# sai_arduinoPinMap.net
KiCad netlist of a schematic drawn in Altium Designer
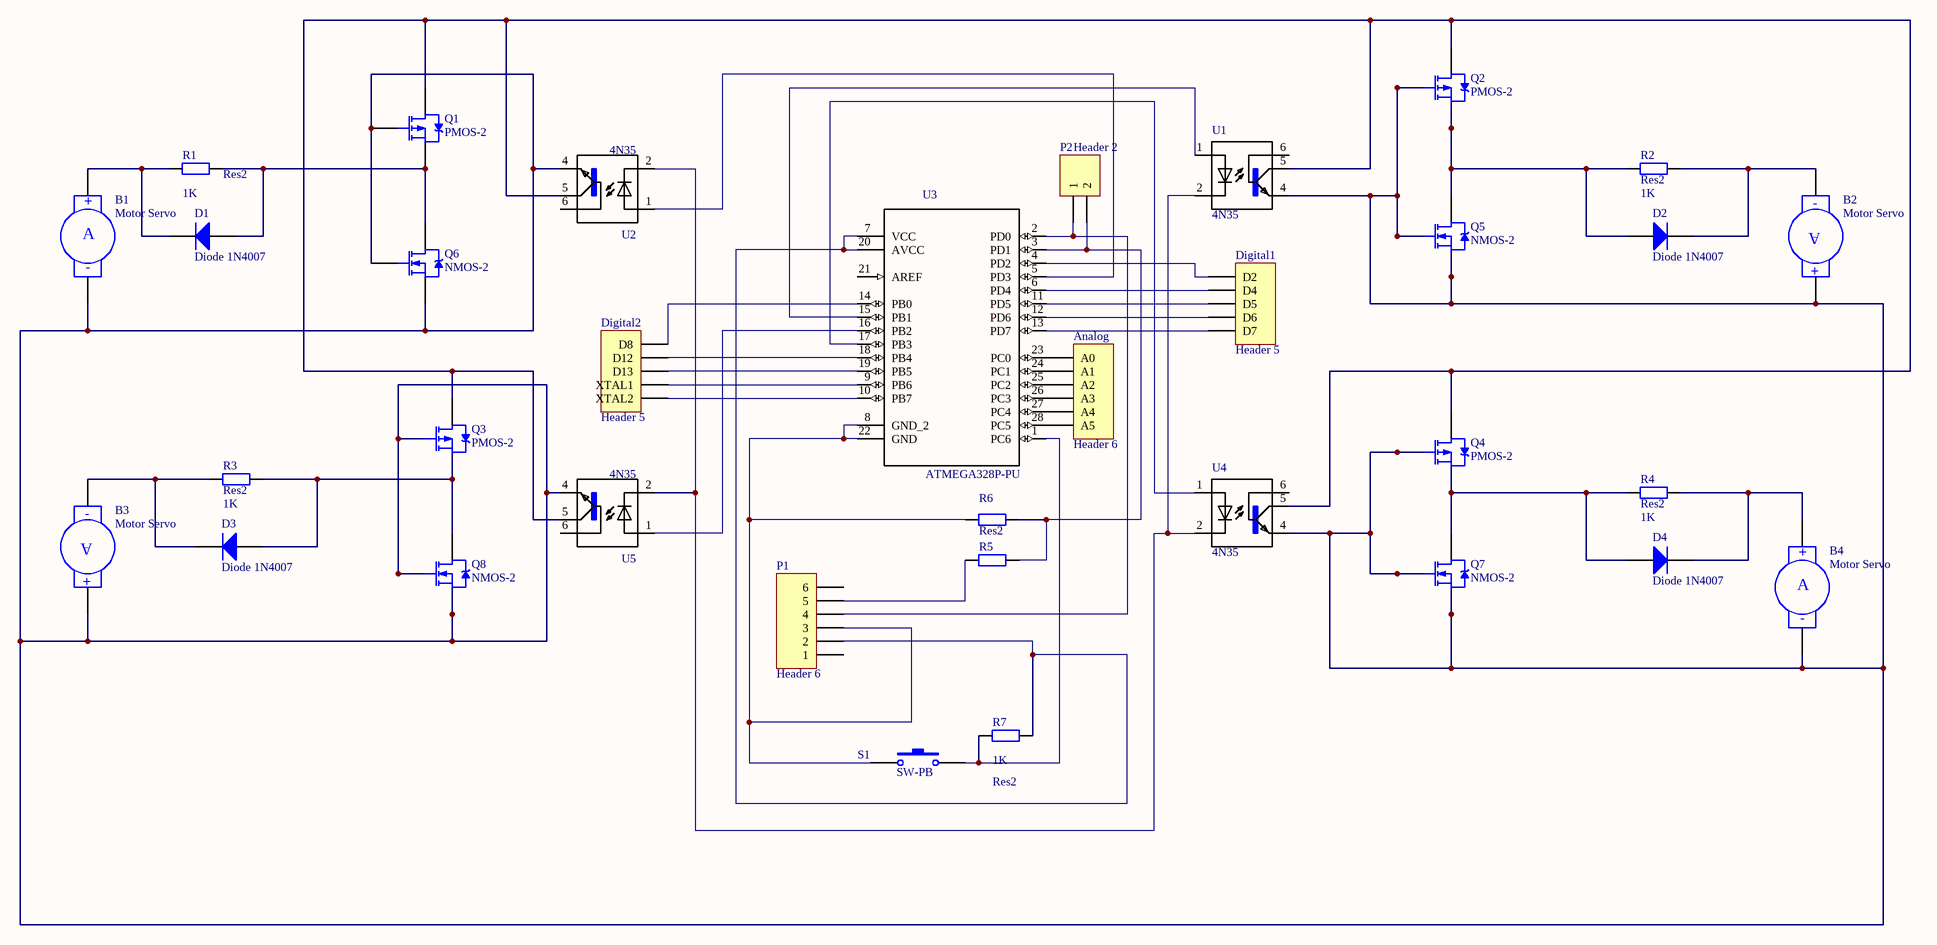
[diagram p0: sai_arduinoPinMap.SchDoc]

(export (version "E")
  (design (tool "Eeschema 10.0.6"))
  (components
    (comp (ref "Analog")
      (value "Header 6")
      (footprint "HDR1X6")
      (description "Header, 6-Pin")
      (fields (field (name "PUBLISHER") "Altium Limited"))
      (libsource (lib "") (part "Header 6_1"))
    )
    (comp (ref "B1")
      (value "Motor Servo")
      (footprint "RAD-0.4")
      (description "Servo Motor")
      (fields (field (name "PUBLISHER") "Altium Limited"))
      (libsource (lib "Miscellaneous Devices") (part "Motor Servo"))
    )
    (comp (ref "B2")
      (value "Motor Servo")
      (footprint "RAD-0.4")
      (description "Servo Motor")
      (fields (field (name "PUBLISHER") "Altium Limited"))
      (libsource (lib "Miscellaneous Devices") (part "Motor Servo"))
    )
    (comp (ref "B3")
      (value "Motor Servo")
      (footprint "RAD-0.4")
      (description "Servo Motor")
      (fields (field (name "PUBLISHER") "Altium Limited"))
      (libsource (lib "Miscellaneous Devices") (part "Motor Servo"))
    )
    (comp (ref "B4")
      (value "Motor Servo")
      (footprint "RAD-0.4")
      (description "Servo Motor")
      (fields (field (name "PUBLISHER") "Altium Limited"))
      (libsource (lib "Miscellaneous Devices") (part "Motor Servo"))
    )
    (comp (ref "D1")
      (value "Diode 1N4007")
      (footprint "DO-41")
      (description "1 Amp General Purpose Rectifier")
      (fields (field (name "PUBLISHER") "Altium Limited"))
      (libsource (lib "Miscellaneous Devices") (part "Diode 1N4007"))
    )
    (comp (ref "D2")
      (value "Diode 1N4007")
      (footprint "DO-41")
      (description "1 Amp General Purpose Rectifier")
      (fields (field (name "PUBLISHER") "Altium Limited"))
      (libsource (lib "Miscellaneous Devices") (part "Diode 1N4007"))
    )
    (comp (ref "D3")
      (value "Diode 1N4007")
      (footprint "DO-41")
      (description "1 Amp General Purpose Rectifier")
      (fields (field (name "PUBLISHER") "Altium Limited"))
      (libsource (lib "Miscellaneous Devices") (part "Diode 1N4007"))
    )
    (comp (ref "D4")
      (value "Diode 1N4007")
      (footprint "DO-41")
      (description "1 Amp General Purpose Rectifier")
      (fields (field (name "PUBLISHER") "Altium Limited"))
      (libsource (lib "Miscellaneous Devices") (part "Diode 1N4007"))
    )
    (comp (ref "Digital1")
      (value "Header 5")
      (footprint "HDR1X5")
      (description "Header, 5-Pin")
      (fields (field (name "PUBLISHER") "Altium Limited"))
      (libsource (lib "Miscellaneous Connectors") (part "Header 5"))
    )
    (comp (ref "Digital2")
      (value "Header 5")
      (footprint "HDR1X5")
      (description "Header, 5-Pin")
      (fields (field (name "PUBLISHER") "Altium Limited"))
      (libsource (lib "") (part "Header 5_1"))
    )
    (comp (ref "P1")
      (value "Header 6")
      (footprint "HDR1X6")
      (description "Header, 6-Pin")
      (fields (field (name "PUBLISHER") "Altium Limited"))
      (libsource (lib "Miscellaneous Connectors") (part "Header 6"))
    )
    (comp (ref "P2")
      (value "Header 2")
      (footprint "HDR1X2")
      (description "Header, 2-Pin")
      (fields (field (name "PUBLISHER") "Altium Limited"))
      (libsource (lib "Miscellaneous Connectors") (part "Header 2"))
    )
    (comp (ref "Q1")
      (value "PMOS-2")
      (footprint "TO-220AB")
      (description "P-Channel Power MOSFET")
      (fields (field (name "PUBLISHER") "Altium Limited"))
      (libsource (lib "Miscellaneous Devices") (part "PMOS-2"))
    )
    (comp (ref "Q2")
      (value "PMOS-2")
      (footprint "TO-220AB")
      (description "P-Channel Power MOSFET")
      (fields (field (name "PUBLISHER") "Altium Limited"))
      (libsource (lib "Miscellaneous Devices") (part "PMOS-2"))
    )
    (comp (ref "Q3")
      (value "PMOS-2")
      (footprint "TO-220AB")
      (description "P-Channel Power MOSFET")
      (fields (field (name "PUBLISHER") "Altium Limited"))
      (libsource (lib "Miscellaneous Devices") (part "PMOS-2"))
    )
    (comp (ref "Q4")
      (value "PMOS-2")
      (footprint "TO-220AB")
      (description "P-Channel Power MOSFET")
      (fields (field (name "PUBLISHER") "Altium Limited"))
      (libsource (lib "Miscellaneous Devices") (part "PMOS-2"))
    )
    (comp (ref "Q5")
      (value "NMOS-2")
      (footprint "TO-220AB")
      (description "N-Channel Power MOSFET")
      (fields (field (name "PUBLISHER") "Altium Limited"))
      (libsource (lib "Miscellaneous Devices") (part "NMOS-2"))
    )
    (comp (ref "Q6")
      (value "NMOS-2")
      (footprint "TO-220AB")
      (description "N-Channel Power MOSFET")
      (fields (field (name "PUBLISHER") "Altium Limited"))
      (libsource (lib "Miscellaneous Devices") (part "NMOS-2"))
    )
    (comp (ref "Q7")
      (value "NMOS-2")
      (footprint "TO-220AB")
      (description "N-Channel Power MOSFET")
      (fields (field (name "PUBLISHER") "Altium Limited"))
      (libsource (lib "Miscellaneous Devices") (part "NMOS-2"))
    )
    (comp (ref "Q8")
      (value "NMOS-2")
      (footprint "TO-220AB")
      (description "N-Channel Power MOSFET")
      (fields (field (name "PUBLISHER") "Altium Limited"))
      (libsource (lib "Miscellaneous Devices") (part "NMOS-2"))
    )
    (comp (ref "R1")
      (value "Res2")
      (footprint "AXIAL-0.4")
      (description "Resistor")
      (fields (field (name "ALTIUM_VALUE") "1K") (field (name "PUBLISHER") "Altium Limited"))
      (libsource (lib "Miscellaneous Devices") (part "Res2"))
    )
    (comp (ref "R2")
      (value "Res2")
      (footprint "AXIAL-0.4")
      (description "Resistor")
      (fields (field (name "ALTIUM_VALUE") "1K") (field (name "PUBLISHER") "Altium Limited"))
      (libsource (lib "Miscellaneous Devices") (part "Res2"))
    )
    (comp (ref "R3")
      (value "Res2")
      (footprint "AXIAL-0.4")
      (description "Resistor")
      (fields (field (name "ALTIUM_VALUE") "1K") (field (name "PUBLISHER") "Altium Limited"))
      (libsource (lib "Miscellaneous Devices") (part "Res2"))
    )
    (comp (ref "R4")
      (value "Res2")
      (footprint "AXIAL-0.4")
      (description "Resistor")
      (fields (field (name "ALTIUM_VALUE") "1K") (field (name "PUBLISHER") "Altium Limited"))
      (libsource (lib "Miscellaneous Devices") (part "Res2"))
    )
    (comp (ref "R5")
      (value "Res2")
      (footprint "AXIAL-0.4")
      (description "Resistor")
      (fields (field (name "PUBLISHER") "Altium Limited"))
      (libsource (lib "") (part "Res2_1"))
    )
    (comp (ref "R6")
      (value "Res2")
      (footprint "AXIAL-0.4")
      (description "Resistor")
      (fields (field (name "PUBLISHER") "Altium Limited"))
      (libsource (lib "Miscellaneous Devices") (part "Res2"))
    )
    (comp (ref "R7")
      (value "Res2")
      (footprint "AXIAL-0.4")
      (description "Resistor")
      (fields (field (name "ALTIUM_VALUE") "1K") (field (name "PUBLISHER") "Altium Limited"))
      (libsource (lib "Miscellaneous Devices") (part "Res2"))
    )
    (comp (ref "S1")
      (value "SW-PB")
      (footprint "SPST-2")
      (description "Switch")
      (fields (field (name "PUBLISHER") "Altium Limited"))
      (libsource (lib "Miscellaneous Devices") (part "SW-PB"))
    )
    (comp (ref "U1")
      (value "4N35")
      (footprint "*DIL06")
      (description "Optoisolator; Analog; 6-Pin DIP; Transistor; 6 PIN SINGLE; 100% CTR;")
      (fields (field (name "MF") "Vishay Semiconductor"))
      (libsource (lib "4N35") (part "4N35"))
    )
    (comp (ref "U2")
      (value "4N35")
      (footprint "*DIL06")
      (description "Optoisolator; Analog; 6-Pin DIP; Transistor; 6 PIN SINGLE; 100% CTR;")
      (fields (field (name "MF") "Vishay Semiconductor"))
      (libsource (lib "4N35") (part "4N35"))
    )
    (comp (ref "U3")
      (value "ATMEGA328P-PU")
      (footprint "*DIP254P762X457-28")
      (description "Embedded microcontroller ATMEGA328P-PU PDIP 28 Microchip Technology 8-Bit 20 MHz I/O number 23")
      (fields (field (name "MF") "Microchip"))
      (libsource (lib "ATMEGA328P-PU") (part "ATMEGA328P-PU"))
    )
    (comp (ref "U4")
      (value "4N35")
      (footprint "*DIL06")
      (description "Optoisolator; Analog; 6-Pin DIP; Transistor; 6 PIN SINGLE; 100% CTR;")
      (fields (field (name "MF") "Vishay Semiconductor"))
      (libsource (lib "4N35") (part "4N35"))
    )
    (comp (ref "U5")
      (value "4N35")
      (footprint "*DIL06")
      (description "Optoisolator; Analog; 6-Pin DIP; Transistor; 6 PIN SINGLE; 100% CTR;")
      (fields (field (name "MF") "Vishay Semiconductor"))
      (libsource (lib "4N35") (part "4N35"))
    )
  )
  (nets
    (net (code "1") (name "Net-(Analog-A0)") (class "Default")
      (node (ref "Analog") (pin "1") (pinfunction "A0_1") (pintype "passive"))
      (node (ref "U3") (pin "23") (pinfunction "PC0_23") (pintype "bidirectional"))
    )
    (net (code "2") (name "Net-(Analog-A1)") (class "Default")
      (node (ref "Analog") (pin "2") (pinfunction "A1_2") (pintype "passive"))
      (node (ref "U3") (pin "24") (pinfunction "PC1_24") (pintype "bidirectional"))
    )
    (net (code "3") (name "Net-(Analog-A2)") (class "Default")
      (node (ref "Analog") (pin "3") (pinfunction "A2_3") (pintype "passive"))
      (node (ref "U3") (pin "25") (pinfunction "PC2_25") (pintype "bidirectional"))
    )
    (net (code "4") (name "Net-(Analog-A3)") (class "Default")
      (node (ref "Analog") (pin "4") (pinfunction "A3_4") (pintype "passive"))
      (node (ref "U3") (pin "26") (pinfunction "PC3_26") (pintype "bidirectional"))
    )
    (net (code "5") (name "Net-(Analog-A4)") (class "Default")
      (node (ref "Analog") (pin "5") (pinfunction "A4_5") (pintype "passive"))
      (node (ref "U3") (pin "27") (pinfunction "PC4_27") (pintype "bidirectional"))
    )
    (net (code "6") (name "Net-(Analog-A5)") (class "Default")
      (node (ref "Analog") (pin "6") (pinfunction "A5_6") (pintype "passive"))
      (node (ref "U3") (pin "28") (pinfunction "PC5_28") (pintype "bidirectional"))
    )
    (net (code "7") (name "Net-(B1-+)") (class "Default")
      (node (ref "B1") (pin "1") (pinfunction "+_1") (pintype "passive"))
      (node (ref "D1") (pin "2") (pinfunction "K_2") (pintype "passive"))
      (node (ref "R1") (pin "1") (pinfunction "1_1") (pintype "passive"))
    )
    (net (code "8") (name "Net-(B1--)") (class "Default")
      (node (ref "B1") (pin "2") (pinfunction "-_2") (pintype "passive"))
      (node (ref "B2") (pin "1") (pinfunction "+_1") (pintype "passive"))
      (node (ref "B3") (pin "1") (pinfunction "+_1") (pintype "passive"))
      (node (ref "B4") (pin "2") (pinfunction "-_2") (pintype "passive"))
      (node (ref "Q1") (pin "1") (pinfunction "G_1") (pintype "passive"))
      (node (ref "Q2") (pin "1") (pinfunction "G_1") (pintype "passive"))
      (node (ref "Q3") (pin "1") (pinfunction "G_1") (pintype "passive"))
      (node (ref "Q4") (pin "1") (pinfunction "G_1") (pintype "passive"))
      (node (ref "Q5") (pin "1") (pinfunction "G_1") (pintype "passive"))
      (node (ref "Q5") (pin "3") (pinfunction "S_3") (pintype "passive"))
      (node (ref "Q6") (pin "1") (pinfunction "G_1") (pintype "passive"))
      (node (ref "Q6") (pin "3") (pinfunction "S_3") (pintype "passive"))
      (node (ref "Q7") (pin "1") (pinfunction "G_1") (pintype "passive"))
      (node (ref "Q7") (pin "3") (pinfunction "S_3") (pintype "passive"))
      (node (ref "Q8") (pin "1") (pinfunction "G_1") (pintype "passive"))
      (node (ref "Q8") (pin "3") (pinfunction "S_3") (pintype "passive"))
      (node (ref "U1") (pin "4") (pinfunction "EMI_4") (pintype "passive"))
      (node (ref "U2") (pin "4") (pinfunction "EMI_4") (pintype "passive"))
      (node (ref "U4") (pin "4") (pinfunction "EMI_4") (pintype "passive"))
      (node (ref "U5") (pin "4") (pinfunction "EMI_4") (pintype "passive"))
    )
    (net (code "9") (name "Net-(B2--)") (class "Default")
      (node (ref "B2") (pin "2") (pinfunction "-_2") (pintype "passive"))
      (node (ref "D2") (pin "2") (pinfunction "K_2") (pintype "passive"))
      (node (ref "R2") (pin "2") (pinfunction "2_2") (pintype "passive"))
    )
    (net (code "10") (name "Net-(B3--)") (class "Default")
      (node (ref "B3") (pin "2") (pinfunction "-_2") (pintype "passive"))
      (node (ref "D3") (pin "2") (pinfunction "K_2") (pintype "passive"))
      (node (ref "R3") (pin "1") (pinfunction "1_1") (pintype "passive"))
    )
    (net (code "11") (name "Net-(B4-+)") (class "Default")
      (node (ref "B4") (pin "1") (pinfunction "+_1") (pintype "passive"))
      (node (ref "D4") (pin "2") (pinfunction "K_2") (pintype "passive"))
      (node (ref "R4") (pin "2") (pinfunction "2_2") (pintype "passive"))
    )
    (net (code "12") (name "Net-(D1-A)") (class "Default")
      (node (ref "D1") (pin "1") (pinfunction "A_1") (pintype "passive"))
      (node (ref "Q1") (pin "3") (pinfunction "S_3") (pintype "passive"))
      (node (ref "Q6") (pin "2") (pinfunction "D_2") (pintype "passive"))
      (node (ref "R1") (pin "2") (pinfunction "2_2") (pintype "passive"))
    )
    (net (code "13") (name "Net-(D2-A)") (class "Default")
      (node (ref "D2") (pin "1") (pinfunction "A_1") (pintype "passive"))
      (node (ref "Q2") (pin "3") (pinfunction "S_3") (pintype "passive"))
      (node (ref "Q5") (pin "2") (pinfunction "D_2") (pintype "passive"))
      (node (ref "R2") (pin "1") (pinfunction "1_1") (pintype "passive"))
    )
    (net (code "14") (name "Net-(D3-A)") (class "Default")
      (node (ref "D3") (pin "1") (pinfunction "A_1") (pintype "passive"))
      (node (ref "Q3") (pin "3") (pinfunction "S_3") (pintype "passive"))
      (node (ref "Q8") (pin "2") (pinfunction "D_2") (pintype "passive"))
      (node (ref "R3") (pin "2") (pinfunction "2_2") (pintype "passive"))
    )
    (net (code "15") (name "Net-(D4-A)") (class "Default")
      (node (ref "D4") (pin "1") (pinfunction "A_1") (pintype "passive"))
      (node (ref "Q4") (pin "3") (pinfunction "S_3") (pintype "passive"))
      (node (ref "Q7") (pin "2") (pinfunction "D_2") (pintype "passive"))
      (node (ref "R4") (pin "1") (pinfunction "1_1") (pintype "passive"))
    )
    (net (code "16") (name "Net-(Digital1-D2)") (class "Default")
      (node (ref "Digital1") (pin "1") (pinfunction "D2_1") (pintype "passive"))
      (node (ref "U3") (pin "4") (pinfunction "PD2_4") (pintype "bidirectional"))
    )
    (net (code "17") (name "Net-(Digital1-D4)") (class "Default")
      (node (ref "Digital1") (pin "2") (pinfunction "D4_2") (pintype "passive"))
      (node (ref "U3") (pin "6") (pinfunction "PD4_6") (pintype "bidirectional"))
    )
    (net (code "18") (name "Net-(Digital1-D5)") (class "Default")
      (node (ref "Digital1") (pin "3") (pinfunction "D5_3") (pintype "passive"))
      (node (ref "U3") (pin "11") (pinfunction "PD5_11") (pintype "bidirectional"))
    )
    (net (code "19") (name "Net-(Digital1-D6)") (class "Default")
      (node (ref "Digital1") (pin "4") (pinfunction "D6_4") (pintype "passive"))
      (node (ref "U3") (pin "12") (pinfunction "PD6_12") (pintype "bidirectional"))
    )
    (net (code "20") (name "Net-(Digital1-D7)") (class "Default")
      (node (ref "Digital1") (pin "5") (pinfunction "D7_5") (pintype "passive"))
      (node (ref "U3") (pin "13") (pinfunction "PD7_13") (pintype "bidirectional"))
    )
    (net (code "21") (name "Net-(Digital2-D8)") (class "Default")
      (node (ref "Digital2") (pin "1") (pinfunction "D8_1") (pintype "passive"))
      (node (ref "U3") (pin "14") (pinfunction "PB0_14") (pintype "bidirectional"))
    )
    (net (code "22") (name "Net-(Digital2-D12)") (class "Default")
      (node (ref "Digital2") (pin "2") (pinfunction "D12_2") (pintype "passive"))
      (node (ref "U3") (pin "18") (pinfunction "PB4_18") (pintype "bidirectional"))
    )
    (net (code "23") (name "Net-(Digital2-D13)") (class "Default")
      (node (ref "Digital2") (pin "3") (pinfunction "D13_3") (pintype "passive"))
      (node (ref "U3") (pin "19") (pinfunction "PB5_19") (pintype "bidirectional"))
    )
    (net (code "24") (name "Net-(Digital2-XTAL1)") (class "Default")
      (node (ref "Digital2") (pin "4") (pinfunction "XTAL1_4") (pintype "passive"))
      (node (ref "U3") (pin "9") (pinfunction "PB6_9") (pintype "bidirectional"))
    )
    (net (code "25") (name "Net-(Digital2-XTAL2)") (class "Default")
      (node (ref "Digital2") (pin "5") (pinfunction "XTAL2_5") (pintype "passive"))
      (node (ref "U3") (pin "10") (pinfunction "PB7_10") (pintype "bidirectional"))
    )
    (net (code "26") (name "Net-(P1-Pad5)") (class "Default")
      (node (ref "P1") (pin "5") (pinfunction "5_5") (pintype "passive"))
      (node (ref "R5") (pin "2") (pinfunction "2_2") (pintype "passive"))
    )
    (net (code "27") (name "Net-(Q1-D)") (class "Default")
      (node (ref "Q1") (pin "2") (pinfunction "D_2") (pintype "passive"))
      (node (ref "Q2") (pin "2") (pinfunction "D_2") (pintype "passive"))
      (node (ref "Q3") (pin "2") (pinfunction "D_2") (pintype "passive"))
      (node (ref "Q4") (pin "2") (pinfunction "D_2") (pintype "passive"))
      (node (ref "U1") (pin "5") (pinfunction "COL_5") (pintype "passive"))
      (node (ref "U2") (pin "5") (pinfunction "COL_5") (pintype "passive"))
      (node (ref "U4") (pin "5") (pinfunction "COL_5") (pintype "passive"))
      (node (ref "U5") (pin "5") (pinfunction "COL_5") (pintype "passive"))
    )
    (net (code "28") (name "Net-(U1-A)") (class "Default")
      (node (ref "U1") (pin "1") (pinfunction "A_1") (pintype "passive"))
      (node (ref "U3") (pin "15") (pinfunction "PB1_15") (pintype "bidirectional"))
    )
    (net (code "29") (name "Net-(U1-C)") (class "Default")
      (node (ref "U1") (pin "2") (pinfunction "C_2") (pintype "passive"))
      (node (ref "U2") (pin "2") (pinfunction "C_2") (pintype "passive"))
      (node (ref "U4") (pin "2") (pinfunction "C_2") (pintype "passive"))
      (node (ref "U5") (pin "2") (pinfunction "C_2") (pintype "passive"))
    )
    (net (code "30") (name "Net-(U2-A)") (class "Default")
      (node (ref "U2") (pin "1") (pinfunction "A_1") (pintype "passive"))
      (node (ref "U3") (pin "5") (pinfunction "PD3_5") (pintype "bidirectional"))
    )
    (net (code "31") (name "Net-(U3-AVCC)") (class "Default")
      (node (ref "P1") (pin "2") (pinfunction "2_2") (pintype "passive"))
      (node (ref "R7") (pin "2") (pinfunction "2_2") (pintype "passive"))
      (node (ref "U3") (pin "20") (pinfunction "AVCC_20") (pintype "power_in"))
      (node (ref "U3") (pin "7") (pinfunction "VCC_7") (pintype "power_in"))
    )
    (net (code "32") (name "Net-(U3-GND)") (class "Default")
      (node (ref "P1") (pin "3") (pinfunction "3_3") (pintype "passive"))
      (node (ref "R6") (pin "1") (pinfunction "1_1") (pintype "passive"))
      (node (ref "S1") (pin "1") (pinfunction "1_1") (pintype "passive"))
      (node (ref "U3") (pin "22") (pinfunction "GND_22") (pintype "passive"))
      (node (ref "U3") (pin "8") (pinfunction "GND_2_8") (pintype "passive"))
    )
    (net (code "33") (name "Net-(U3-PB2)") (class "Default")
      (node (ref "U3") (pin "16") (pinfunction "PB2_16") (pintype "bidirectional"))
      (node (ref "U5") (pin "1") (pinfunction "A_1") (pintype "passive"))
    )
    (net (code "34") (name "Net-(U3-PB3)") (class "Default")
      (node (ref "U3") (pin "17") (pinfunction "PB3_17") (pintype "bidirectional"))
      (node (ref "U4") (pin "1") (pinfunction "A_1") (pintype "passive"))
    )
    (net (code "35") (name "Net-(U3-PC6)") (class "Default")
      (node (ref "R7") (pin "1") (pinfunction "1_1") (pintype "passive"))
      (node (ref "S1") (pin "2") (pinfunction "2_2") (pintype "passive"))
      (node (ref "U3") (pin "1") (pinfunction "PC6_1") (pintype "bidirectional"))
    )
    (net (code "36") (name "Net-(U3-PD0)") (class "Default")
      (node (ref "P1") (pin "4") (pinfunction "4_4") (pintype "passive"))
      (node (ref "P2") (pin "1") (pinfunction "1_1") (pintype "passive"))
      (node (ref "U3") (pin "2") (pinfunction "PD0_2") (pintype "bidirectional"))
    )
    (net (code "37") (name "Net-(U3-PD1)") (class "Default")
      (node (ref "P2") (pin "2") (pinfunction "2_2") (pintype "passive"))
      (node (ref "R5") (pin "1") (pinfunction "1_1") (pintype "passive"))
      (node (ref "R6") (pin "2") (pinfunction "2_2") (pintype "passive"))
      (node (ref "U3") (pin "3") (pinfunction "PD1_3") (pintype "bidirectional"))
    )
    (net (code "38") (name "unconnected-(P1-Pad1)") (class "Default")
      (node (ref "P1") (pin "1") (pinfunction "1_1") (pintype "passive"))
    )
    (net (code "39") (name "unconnected-(P1-Pad6)") (class "Default")
      (node (ref "P1") (pin "6") (pinfunction "6_6") (pintype "passive"))
    )
    (net (code "40") (name "unconnected-(U1-BAS-Pad6)") (class "Default")
      (node (ref "U1") (pin "6") (pinfunction "BAS_6") (pintype "passive"))
    )
    (net (code "41") (name "unconnected-(U2-BAS-Pad6)") (class "Default")
      (node (ref "U2") (pin "6") (pinfunction "BAS_6") (pintype "passive"))
    )
    (net (code "42") (name "unconnected-(U3-AREF-Pad21)") (class "Default")
      (node (ref "U3") (pin "21") (pinfunction "AREF_21") (pintype "input"))
    )
    (net (code "43") (name "unconnected-(U4-BAS-Pad6)") (class "Default")
      (node (ref "U4") (pin "6") (pinfunction "BAS_6") (pintype "passive"))
    )
    (net (code "44") (name "unconnected-(U5-BAS-Pad6)") (class "Default")
      (node (ref "U5") (pin "6") (pinfunction "BAS_6") (pintype "passive"))
    )
  )
)
